# CATS-Vega-Frontend.net
KiCad netlist of a schematic drawn in Altium Designer
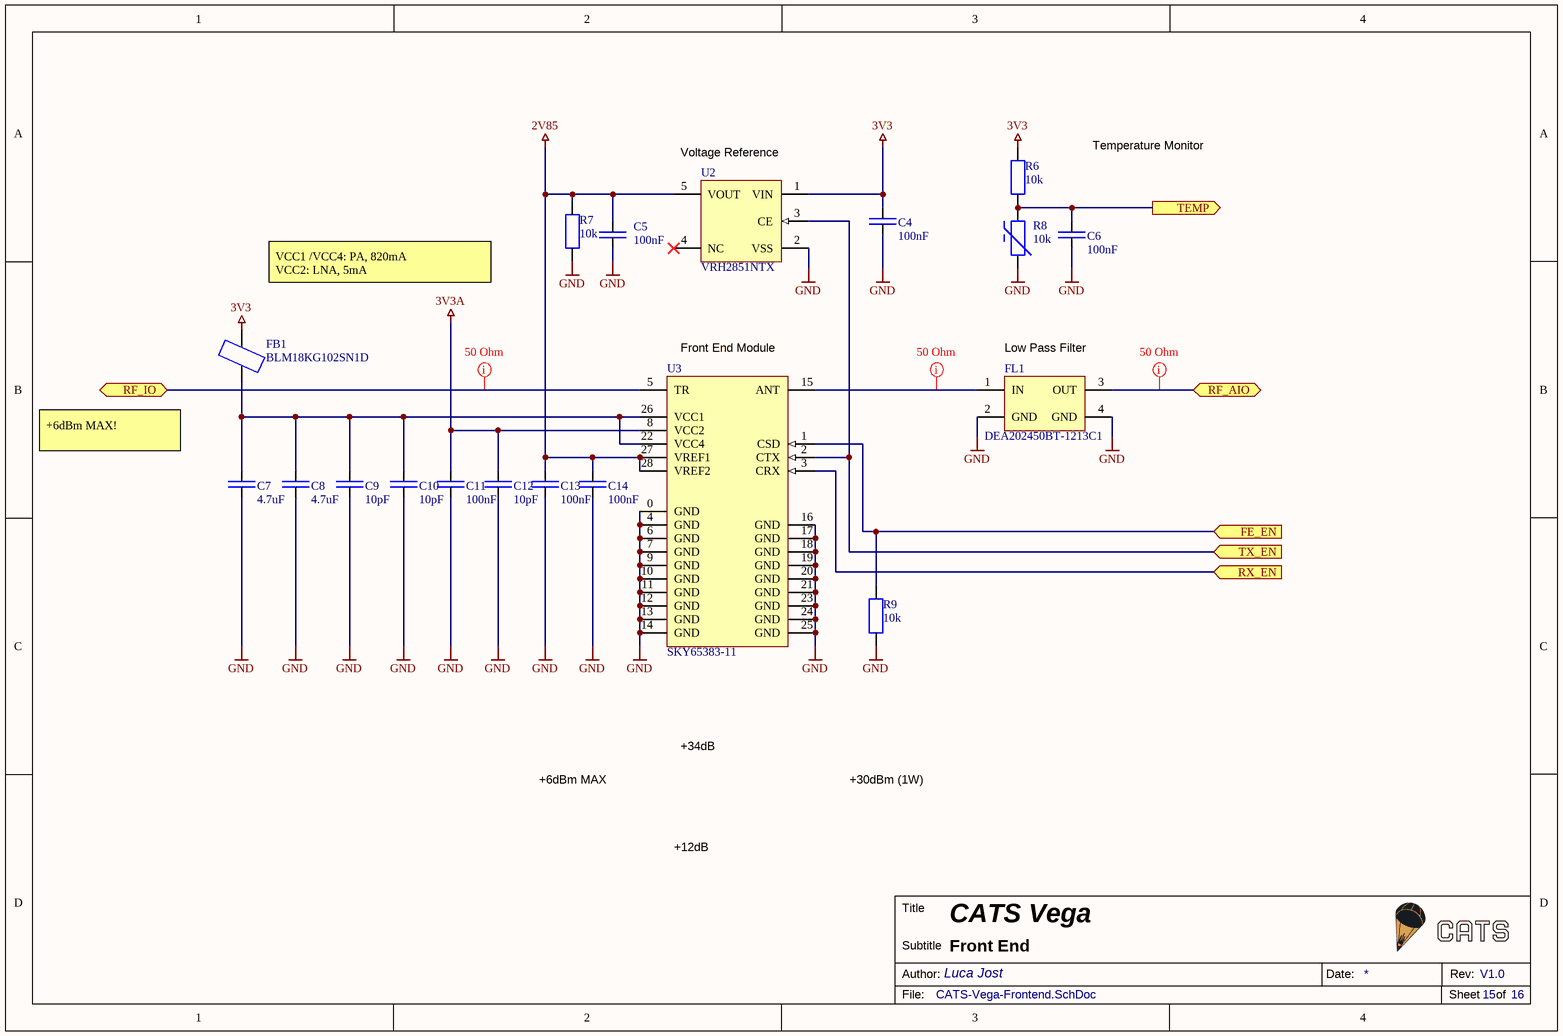
[diagram p0: CATS-Vega-Frontend.SchDoc]

(export (version "E")
  (design (tool "Eeschema 10.0.6"))
  (components
    (comp (ref "C4")
      (value "100nF")
      (footprint "SMD Keramikkondensator 0603")
      (description "SMD Ceramic Capacitor E6")
      (libsource (lib "CATS-EUROC") (part "E6 - 100nF"))
    )
    (comp (ref "C5")
      (value "100nF")
      (footprint "SMD Keramikkondensator 0603")
      (description "SMD Ceramic Capacitor E6")
      (libsource (lib "CATS-EUROC") (part "E6 - 100nF"))
    )
    (comp (ref "C6")
      (value "100nF")
      (footprint "SMD Keramikkondensator 0603")
      (description "SMD Ceramic Capacitor E6")
      (libsource (lib "CATS-EUROC") (part "E6 - 100nF"))
    )
    (comp (ref "C7")
      (value "4.7uF")
      (footprint "SMD Keramikkondensator 0603")
      (description "SMD Ceramic Capacitor E6")
      (libsource (lib "CATS-EUROC") (part "E6 - 4.7uF"))
    )
    (comp (ref "C8")
      (value "4.7uF")
      (footprint "SMD Keramikkondensator 0603")
      (description "SMD Ceramic Capacitor E6")
      (libsource (lib "CATS-EUROC") (part "E6 - 4.7uF"))
    )
    (comp (ref "C9")
      (value "10pF")
      (footprint "SMD Keramikkondensator 0603")
      (description "SMD Ceramic Capacitor E6")
      (libsource (lib "CATS-EUROC") (part "E6 - 10pF"))
    )
    (comp (ref "C10")
      (value "10pF")
      (footprint "SMD Keramikkondensator 0603")
      (description "SMD Ceramic Capacitor E6")
      (libsource (lib "CATS-EUROC") (part "E6 - 10pF"))
    )
    (comp (ref "C11")
      (value "100nF")
      (footprint "SMD Keramikkondensator 0603")
      (description "SMD Ceramic Capacitor E6")
      (libsource (lib "CATS-EUROC") (part "E6 - 100nF"))
    )
    (comp (ref "C12")
      (value "10pF")
      (footprint "SMD Keramikkondensator 0603")
      (description "SMD Ceramic Capacitor E6")
      (libsource (lib "CATS-EUROC") (part "E6 - 10pF"))
    )
    (comp (ref "C13")
      (value "100nF")
      (footprint "SMD Keramikkondensator 0603")
      (description "SMD Ceramic Capacitor E6")
      (libsource (lib "CATS-EUROC") (part "E6 - 100nF"))
    )
    (comp (ref "C14")
      (value "100nF")
      (footprint "SMD Keramikkondensator 0603")
      (description "SMD Ceramic Capacitor E6")
      (libsource (lib "CATS-EUROC") (part "E6 - 100nF"))
    )
    (comp (ref "FB1")
      (value "BLM18KG102SN1D")
      (footprint "SMD Ferrite Bead 0603")
      (description "1 kOhms @ 100MHz 1 Power Line Ferrite Bead 0603 (1608 Metric) 1A 200mOhm")
      (libsource (lib "CATS-EUROC") (part "BLM18KG102SN1D"))
    )
    (comp (ref "FL1")
      (value "DEA202450BT-1213C1")
      (footprint "SMD Filter DEA202450BT")
      (description "Multilayer Band Pass Filter 2400-2500MHz")
      (libsource (lib "RF") (part "DEA202450BT-1213C1"))
    )
    (comp (ref "R6")
      (value "10k")
      (footprint "SMD Widerstand 0603")
      (description "SMD Chip Resistor E24")
      (libsource (lib "CATS-EUROC") (part "E24 - 10k"))
    )
    (comp (ref "R7")
      (value "10k")
      (footprint "SMD Widerstand 0603")
      (description "SMD Chip Resistor E24")
      (libsource (lib "CATS-EUROC") (part "E24 - 10k"))
    )
    (comp (ref "R8")
      (value "10k")
      (footprint "SMD NTC 0603")
      (description "NTC 10kΩ -55℃~+125℃ 0.31mA 100mW ±1% 3450K")
      (libsource (lib "Sensors") (part "SDNT1608X103F3450FTF"))
    )
    (comp (ref "R9")
      (value "10k")
      (footprint "SMD Widerstand 0603")
      (description "SMD Chip Resistor E24")
      (libsource (lib "CATS-EUROC") (part "E24 - 10k"))
    )
    (comp (ref "U2")
      (value "VRH2851NTX")
      (footprint "SMD IC SOT-23-5")
      (description "Linear Voltage Regulator IC Positive Fixed 1 Output  250mA SOT-23-5 2.85V")
      (libsource (lib "Voltage-Converter") (part "VRH2851NTX"))
    )
    (comp (ref "U3")
      (value "SKY65383-11")
      (footprint "SMD IC 28-MCM")
      (description "2400 to 2483 MHz Transmit/Receive\r\nFront-End Module +30dBm")
      (libsource (lib "RF") (part "SKY65383-11"))
    )
  )
  (nets
    (net (code "1") (name "/FE_EN") (class "Default")
      (node (ref "R9") (pin "2") (pinfunction "2_2") (pintype "passive"))
      (node (ref "U3") (pin "1") (pinfunction "CSD_1") (pintype "input"))
    )
    (net (code "2") (name "/RF_AIO") (class "Default")
      (node (ref "FL1") (pin "3") (pinfunction "OUT_3") (pintype "passive"))
    )
    (net (code "3") (name "/RF_IO") (class "Default")
      (node (ref "U3") (pin "5") (pinfunction "TR_5") (pintype "passive"))
    )
    (net (code "4") (name "/RX_EN") (class "Default")
      (node (ref "U3") (pin "3") (pinfunction "CRX_3") (pintype "input"))
    )
    (net (code "5") (name "/TEMP") (class "Default")
      (node (ref "C6") (pin "2") (pinfunction "2_2") (pintype "passive"))
      (node (ref "R6") (pin "1") (pinfunction "1_1") (pintype "passive"))
      (node (ref "R8") (pin "1") (pinfunction "1_1") (pintype "passive"))
    )
    (net (code "6") (name "/TX_EN") (class "Default")
      (node (ref "U2") (pin "3") (pinfunction "CE_3") (pintype "input"))
      (node (ref "U3") (pin "2") (pinfunction "CTX_2") (pintype "input"))
    )
    (net (code "7") (name "2V85") (class "Default")
      (node (ref "C13") (pin "2") (pinfunction "2_2") (pintype "passive"))
      (node (ref "C14") (pin "2") (pinfunction "2_2") (pintype "passive"))
      (node (ref "C5") (pin "2") (pinfunction "2_2") (pintype "passive"))
      (node (ref "R7") (pin "2") (pinfunction "2_2") (pintype "passive"))
      (node (ref "U2") (pin "5") (pinfunction "VOUT_5") (pintype "passive"))
      (node (ref "U3") (pin "27") (pinfunction "VREF1_27") (pintype "passive"))
      (node (ref "U3") (pin "28") (pinfunction "VREF2_28") (pintype "passive"))
    )
    (net (code "8") (name "3V3") (class "Default")
      (node (ref "C4") (pin "2") (pinfunction "2_2") (pintype "passive"))
      (node (ref "FB1") (pin "2") (pinfunction "2_2") (pintype "passive"))
      (node (ref "R6") (pin "2") (pinfunction "2_2") (pintype "passive"))
      (node (ref "U2") (pin "1") (pinfunction "VIN_1") (pintype "passive"))
    )
    (net (code "9") (name "3V3A") (class "Default")
      (node (ref "C11") (pin "2") (pinfunction "2_2") (pintype "passive"))
      (node (ref "C12") (pin "2") (pinfunction "2_2") (pintype "passive"))
      (node (ref "U3") (pin "8") (pinfunction "VCC2_8") (pintype "passive"))
    )
    (net (code "10") (name "GND") (class "Default")
      (node (ref "C10") (pin "1") (pinfunction "1_1") (pintype "passive"))
      (node (ref "C11") (pin "1") (pinfunction "1_1") (pintype "passive"))
      (node (ref "C12") (pin "1") (pinfunction "1_1") (pintype "passive"))
      (node (ref "C13") (pin "1") (pinfunction "1_1") (pintype "passive"))
      (node (ref "C14") (pin "1") (pinfunction "1_1") (pintype "passive"))
      (node (ref "C4") (pin "1") (pinfunction "1_1") (pintype "passive"))
      (node (ref "C5") (pin "1") (pinfunction "1_1") (pintype "passive"))
      (node (ref "C6") (pin "1") (pinfunction "1_1") (pintype "passive"))
      (node (ref "C7") (pin "1") (pinfunction "1_1") (pintype "passive"))
      (node (ref "C8") (pin "1") (pinfunction "1_1") (pintype "passive"))
      (node (ref "C9") (pin "1") (pinfunction "1_1") (pintype "passive"))
      (node (ref "FL1") (pin "2") (pinfunction "GND_2") (pintype "passive"))
      (node (ref "FL1") (pin "4") (pinfunction "GND_4") (pintype "passive"))
      (node (ref "R7") (pin "1") (pinfunction "1_1") (pintype "passive"))
      (node (ref "R8") (pin "2") (pinfunction "2_2") (pintype "passive"))
      (node (ref "R9") (pin "1") (pinfunction "1_1") (pintype "passive"))
      (node (ref "U2") (pin "2") (pinfunction "VSS_2") (pintype "passive"))
      (node (ref "U3") (pin "0") (pinfunction "GND_0") (pintype "passive"))
      (node (ref "U3") (pin "10") (pinfunction "GND_10") (pintype "passive"))
      (node (ref "U3") (pin "11") (pinfunction "GND_11") (pintype "passive"))
      (node (ref "U3") (pin "12") (pinfunction "GND_12") (pintype "passive"))
      (node (ref "U3") (pin "13") (pinfunction "GND_13") (pintype "passive"))
      (node (ref "U3") (pin "14") (pinfunction "GND_14") (pintype "passive"))
      (node (ref "U3") (pin "16") (pinfunction "GND_16") (pintype "passive"))
      (node (ref "U3") (pin "17") (pinfunction "GND_17") (pintype "passive"))
      (node (ref "U3") (pin "18") (pinfunction "GND_18") (pintype "passive"))
      (node (ref "U3") (pin "19") (pinfunction "GND_19") (pintype "passive"))
      (node (ref "U3") (pin "20") (pinfunction "GND_20") (pintype "passive"))
      (node (ref "U3") (pin "21") (pinfunction "GND_21") (pintype "passive"))
      (node (ref "U3") (pin "23") (pinfunction "GND_23") (pintype "passive"))
      (node (ref "U3") (pin "24") (pinfunction "GND_24") (pintype "passive"))
      (node (ref "U3") (pin "25") (pinfunction "GND_25") (pintype "passive"))
      (node (ref "U3") (pin "4") (pinfunction "GND_4") (pintype "passive"))
      (node (ref "U3") (pin "6") (pinfunction "GND_6") (pintype "passive"))
      (node (ref "U3") (pin "7") (pinfunction "GND_7") (pintype "passive"))
      (node (ref "U3") (pin "9") (pinfunction "GND_9") (pintype "passive"))
    )
    (net (code "11") (name "Net-(FL1-IN)") (class "Default")
      (node (ref "FL1") (pin "1") (pinfunction "IN_1") (pintype "passive"))
      (node (ref "U3") (pin "15") (pinfunction "ANT_15") (pintype "passive"))
    )
    (net (code "12") (name "Net-(U3-VCC1)") (class "Default")
      (node (ref "C10") (pin "2") (pinfunction "2_2") (pintype "passive"))
      (node (ref "C7") (pin "2") (pinfunction "2_2") (pintype "passive"))
      (node (ref "C8") (pin "2") (pinfunction "2_2") (pintype "passive"))
      (node (ref "C9") (pin "2") (pinfunction "2_2") (pintype "passive"))
      (node (ref "FB1") (pin "1") (pinfunction "1_1") (pintype "passive"))
      (node (ref "U3") (pin "22") (pinfunction "VCC4_22") (pintype "passive"))
      (node (ref "U3") (pin "26") (pinfunction "VCC1_26") (pintype "passive"))
    )
    (net (code "13") (name "unconnected-(U2-NC-Pad4)") (class "Default")
      (node (ref "U2") (pin "4") (pinfunction "NC_4") (pintype "passive+no_connect"))
    )
  )
)
